# MAIN.net
KiCad netlist of a schematic drawn in EAGLE
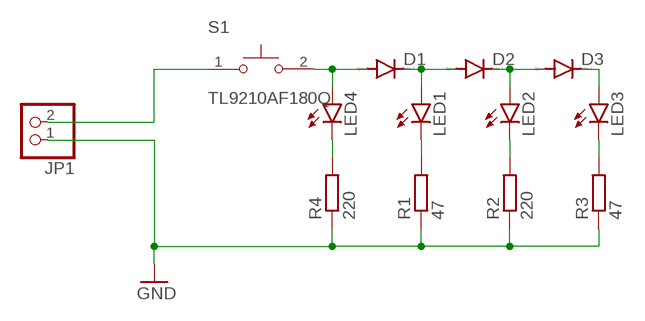
[diagram p0: schematic, sheet 1]

(export (version "E")
  (design (tool "Eeschema 10.0.6"))
  (components
    (comp (ref "D1")
      (value "DIODE-SMB")
      (footprint "eagle-import:SMB")
      (libsource (lib "eagle-import") (part "DIODE-SMB"))
    )
    (comp (ref "D2")
      (value "DIODE-SMB")
      (footprint "eagle-import:SMB")
      (libsource (lib "eagle-import") (part "DIODE-SMB"))
    )
    (comp (ref "D3")
      (value "DIODE-SMB")
      (footprint "eagle-import:SMB")
      (libsource (lib "eagle-import") (part "DIODE-SMB"))
    )
    (comp (ref "JP1")
      (value "PINHD-1X2")
      (footprint "eagle-import:1X02")
      (libsource (lib "eagle-import") (part "PINHD-1X2"))
    )
    (comp (ref "LED1")
      (value "LED5MM")
      (footprint "eagle-import:LED5MM")
      (libsource (lib "eagle-import") (part "LED5MM"))
    )
    (comp (ref "LED2")
      (value "LED5MM")
      (footprint "eagle-import:LED5MM")
      (libsource (lib "eagle-import") (part "LED5MM"))
    )
    (comp (ref "LED3")
      (value "LED5MM")
      (footprint "eagle-import:LED5MM")
      (libsource (lib "eagle-import") (part "LED5MM"))
    )
    (comp (ref "LED4")
      (value "LED5MM")
      (footprint "eagle-import:LED5MM")
      (libsource (lib "eagle-import") (part "LED5MM"))
    )
    (comp (ref "R1")
      (value "47")
      (footprint "eagle-import:R0805")
      (libsource (lib "eagle-import") (part "R-EU_R0805"))
    )
    (comp (ref "R2")
      (value "220")
      (footprint "eagle-import:R0805")
      (libsource (lib "eagle-import") (part "R-EU_R0805"))
    )
    (comp (ref "R3")
      (value "47")
      (footprint "eagle-import:R0805")
      (libsource (lib "eagle-import") (part "R-EU_R0805"))
    )
    (comp (ref "R4")
      (value "220")
      (footprint "eagle-import:R0805")
      (libsource (lib "eagle-import") (part "R-EU_R0805"))
    )
    (comp (ref "S1")
      (value "TL9210AF180Q")
      (footprint "eagle-import:SW_TL9210AF180Q")
      (fields (field (name "MF") "E-Switch"))
      (libsource (lib "eagle-import") (part "TL9210AF180Q"))
    )
  )
  (nets
    (net (code "1") (name "GND") (class "Default")
      (node (ref "JP1") (pin "1") (pinfunction "1_1") (pintype "passive"))
      (node (ref "R1") (pin "1") (pinfunction "1_1") (pintype "passive"))
      (node (ref "R2") (pin "1") (pinfunction "1_1") (pintype "passive"))
      (node (ref "R3") (pin "1") (pinfunction "1_1") (pintype "passive"))
      (node (ref "R4") (pin "1") (pinfunction "1_1") (pintype "passive"))
    )
    (net (code "2") (name "Net-(D1-PadA)") (class "Default")
      (node (ref "D1") (pin "A") (pinfunction "A_A") (pintype "passive"))
      (node (ref "LED4") (pin "A") (pinfunction "A_A") (pintype "passive"))
      (node (ref "S1") (pin "2") (pinfunction "2_2") (pintype "passive"))
    )
    (net (code "3") (name "Net-(D1-PadC)") (class "Default")
      (node (ref "D1") (pin "C") (pinfunction "C_C") (pintype "passive"))
      (node (ref "D2") (pin "A") (pinfunction "A_A") (pintype "passive"))
      (node (ref "LED1") (pin "A") (pinfunction "A_A") (pintype "passive"))
    )
    (net (code "4") (name "Net-(D2-PadC)") (class "Default")
      (node (ref "D2") (pin "C") (pinfunction "C_C") (pintype "passive"))
      (node (ref "D3") (pin "A") (pinfunction "A_A") (pintype "passive"))
      (node (ref "LED2") (pin "A") (pinfunction "A_A") (pintype "passive"))
    )
    (net (code "5") (name "Net-(D3-PadC)") (class "Default")
      (node (ref "D3") (pin "C") (pinfunction "C_C") (pintype "passive"))
      (node (ref "LED3") (pin "A") (pinfunction "A_A") (pintype "passive"))
    )
    (net (code "6") (name "Net-(JP1-Pad2)") (class "Default")
      (node (ref "JP1") (pin "2") (pinfunction "2_2") (pintype "passive"))
      (node (ref "S1") (pin "1") (pinfunction "1_1") (pintype "passive"))
    )
    (net (code "7") (name "Net-(LED1-C)") (class "Default")
      (node (ref "LED1") (pin "K") (pinfunction "C_K") (pintype "passive"))
      (node (ref "R1") (pin "2") (pinfunction "2_2") (pintype "passive"))
    )
    (net (code "8") (name "Net-(LED2-C)") (class "Default")
      (node (ref "LED2") (pin "K") (pinfunction "C_K") (pintype "passive"))
      (node (ref "R2") (pin "2") (pinfunction "2_2") (pintype "passive"))
    )
    (net (code "9") (name "Net-(LED3-C)") (class "Default")
      (node (ref "LED3") (pin "K") (pinfunction "C_K") (pintype "passive"))
      (node (ref "R3") (pin "2") (pinfunction "2_2") (pintype "passive"))
    )
    (net (code "10") (name "Net-(LED4-C)") (class "Default")
      (node (ref "LED4") (pin "K") (pinfunction "C_K") (pintype "passive"))
      (node (ref "R4") (pin "2") (pinfunction "2_2") (pintype "passive"))
    )
  )
)
